# 02.net
KiCad netlist of a schematic drawn in Altium Designer
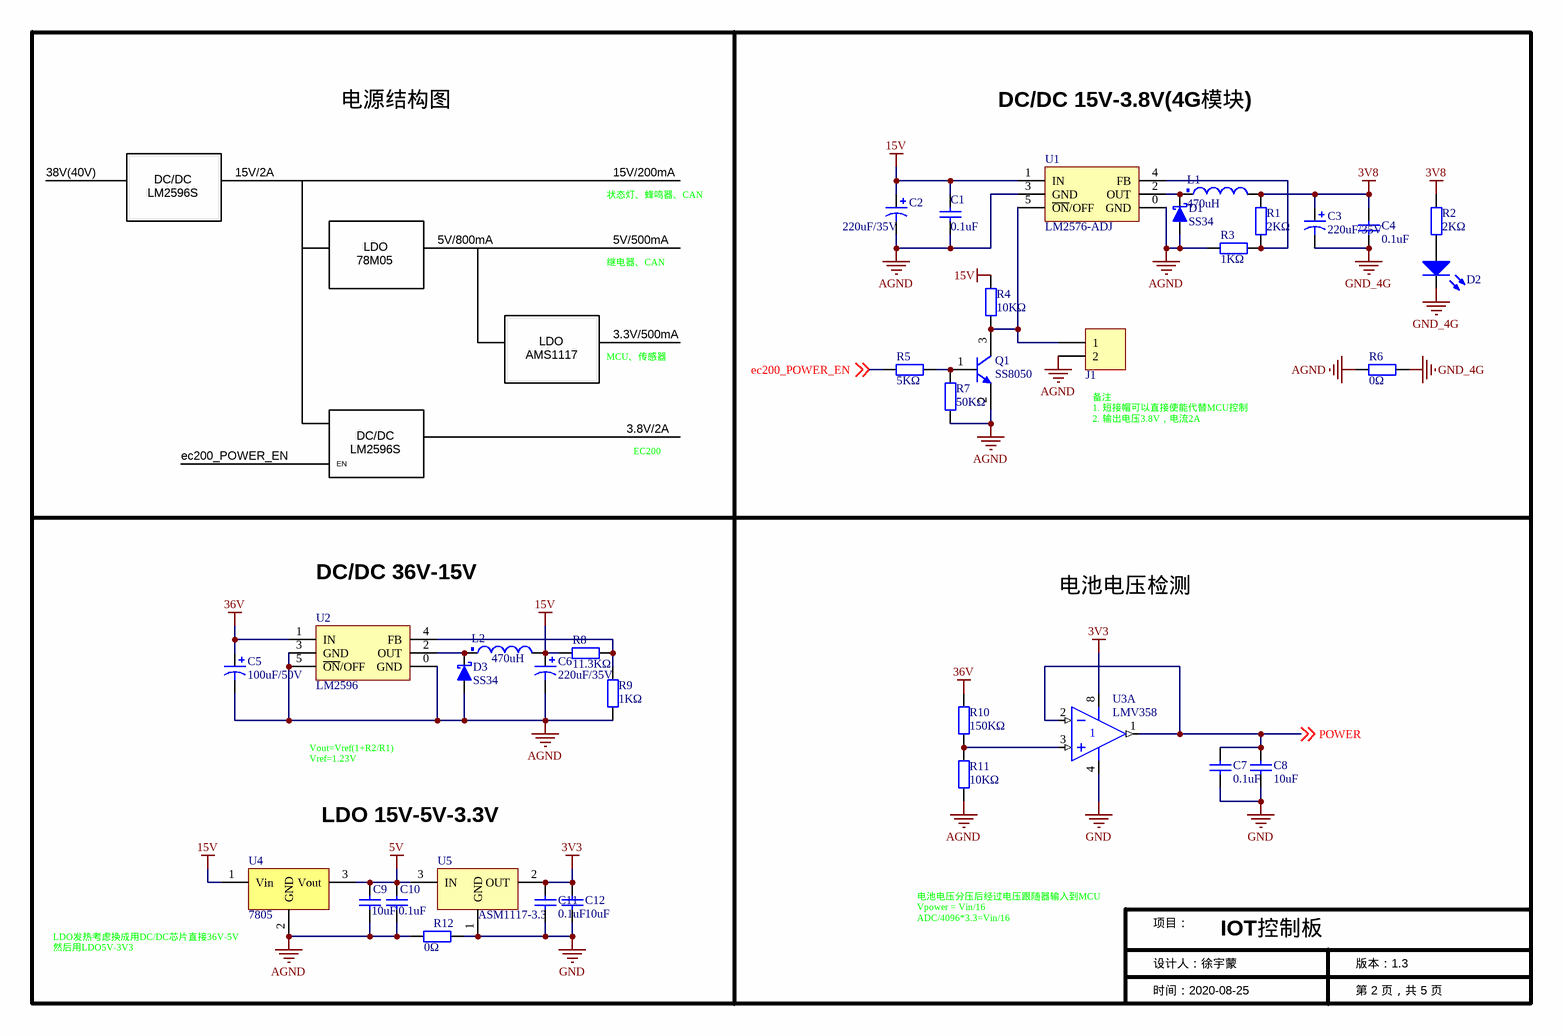
[diagram p0: 02_电源部分.SchDoc]

(export (version "E")
  (design (tool "Eeschema 10.0.6"))
  (components
    (comp (ref "C1")
      (value "0.1uF")
      (footprint "CAP-0603")
      (description "无极性电容")
      (fields (field (name "Comment") "Cap") (field (name "PUBLISHER") "Altium Limited"))
      (libsource (lib "Arrowy_Racing") (part "Cap"))
    )
    (comp (ref "C2")
      (value "220uF/35V")
      (footprint "Cap8x10.5mm")
      (description "贴片电解电容 8*10.5mm")
      (fields (field (name "Comment") "Cap Pol") (field (name "PUBLISHER") "Altium Limited"))
      (libsource (lib "元件库") (part "Cap Pol"))
    )
    (comp (ref "C3")
      (value "220uF/35V")
      (footprint "Cap8x10.5mm")
      (description "贴片电解电容 8*10.5mm")
      (fields (field (name "Comment") "Cap Pol") (field (name "PUBLISHER") "Altium Limited"))
      (libsource (lib "元件库") (part "Cap Pol"))
    )
    (comp (ref "C4")
      (value "0.1uF")
      (footprint "CAP-0603")
      (description "无极性电容")
      (fields (field (name "Comment") "Cap") (field (name "PUBLISHER") "Altium Limited"))
      (libsource (lib "Arrowy_Racing") (part "Cap"))
    )
    (comp (ref "C5")
      (value "100uF/50V")
      (footprint "Cap8x10.5mm")
      (description "贴片电解电容 8*10.5mm")
      (fields (field (name "Comment") "Cap Pol") (field (name "PUBLISHER") "Altium Limited"))
      (libsource (lib "元件库") (part "Cap Pol"))
    )
    (comp (ref "C6")
      (value "220uF/35V")
      (footprint "Cap8x10.5mm")
      (description "贴片电解电容 8*10.5mm")
      (fields (field (name "Comment") "Cap Pol") (field (name "PUBLISHER") "Altium Limited"))
      (libsource (lib "元件库") (part "Cap Pol"))
    )
    (comp (ref "C7")
      (value "0.1uF")
      (footprint "CAP-0603")
      (description "无极性电容")
      (fields (field (name "Comment") "Cap") (field (name "PUBLISHER") "Altium Limited"))
      (libsource (lib "Arrowy_Racing") (part "Cap"))
    )
    (comp (ref "C8")
      (value "10uF")
      (footprint "CAP-0603")
      (description "无极性电容")
      (fields (field (name "Comment") "Cap") (field (name "PUBLISHER") "Altium Limited"))
      (libsource (lib "Arrowy_Racing") (part "Cap"))
    )
    (comp (ref "C9")
      (value "10uF")
      (footprint "CAP-0603")
      (description "无极性电容")
      (fields (field (name "Comment") "Cap") (field (name "PUBLISHER") "Altium Limited"))
      (libsource (lib "Arrowy_Racing") (part "Cap"))
    )
    (comp (ref "C10")
      (value "0.1uF")
      (footprint "CAP-0603")
      (description "无极性电容")
      (fields (field (name "Comment") "Cap") (field (name "PUBLISHER") "Altium Limited"))
      (libsource (lib "Arrowy_Racing") (part "Cap"))
    )
    (comp (ref "C11")
      (value "0.1uF")
      (footprint "CAP-0603")
      (description "无极性电容")
      (fields (field (name "Comment") "Cap") (field (name "PUBLISHER") "Altium Limited"))
      (libsource (lib "Arrowy_Racing") (part "Cap"))
    )
    (comp (ref "C12")
      (value "10uF")
      (footprint "CAP-0603")
      (description "无极性电容")
      (fields (field (name "Comment") "Cap") (field (name "PUBLISHER") "Altium Limited"))
      (libsource (lib "Arrowy_Racing") (part "Cap"))
    )
    (comp (ref "D1")
      (value "SS34")
      (footprint "SMA(DO-214AC)")
      (description "Schottky Diode")
      (fields (field (name "PUBLISHER") "Altium Limited"))
      (libsource (lib "元件库") (part "D Schottky"))
    )
    (comp (ref "D2")
      (value "LED")
      (footprint "LED_0805")
      (description "发光二极管")
      (fields (field (name "PUBLISHER") "Altium Limited"))
      (libsource (lib "Arrowy_Racing") (part "LED"))
    )
    (comp (ref "D3")
      (value "SS34")
      (footprint "SMA(DO-214AC)")
      (description "Schottky Diode")
      (fields (field (name "PUBLISHER") "Altium Limited"))
      (libsource (lib "元件库") (part "D Schottky"))
    )
    (comp (ref "J1")
      (value "Header 2")
      (footprint "Header_2X1_2.54")
      (description "接插件")
      (fields (field (name "PUBLISHER") "Altium Limited"))
      (libsource (lib "Arrowy_Racing") (part "Header 2"))
    )
    (comp (ref "L1")
      (value "470uH")
      (footprint "CD43")
      (description "贴片功率电感")
      (fields (field (name "Comment") "Inductor") (field (name "PUBLISHER") "Altium Limited"))
      (libsource (lib "元件库") (part "Inductor"))
    )
    (comp (ref "L2")
      (value "470uH")
      (footprint "CD43")
      (description "贴片功率电感")
      (fields (field (name "Comment") "Inductor") (field (name "PUBLISHER") "Altium Limited"))
      (libsource (lib "元件库") (part "Inductor"))
    )
    (comp (ref "Q1")
      (value "SS8050")
      (footprint "SOT-23")
      (description "NPN贴片三极管")
      (fields (field (name "PUBLISHER") "Altium Limited"))
      (libsource (lib "Arrowy_Racing") (part "SS8050"))
    )
    (comp (ref "R1")
      (value "2KΩ")
      (footprint "0603")
      (description "贴片电阻")
      (fields (field (name "Comment") "Res") (field (name "PUBLISHER") "Altium Limited"))
      (libsource (lib "") (part "Res_2"))
    )
    (comp (ref "R2")
      (value "2KΩ")
      (footprint "0603")
      (description "贴片电阻")
      (fields (field (name "Comment") "Res") (field (name "PUBLISHER") "Altium Limited"))
      (libsource (lib "Arrowy_Racing") (part "Res"))
    )
    (comp (ref "R3")
      (value "1KΩ")
      (footprint "0603")
      (description "贴片电阻")
      (fields (field (name "Comment") "Res") (field (name "PUBLISHER") "Altium Limited"))
      (libsource (lib "") (part "Res_1"))
    )
    (comp (ref "R4")
      (value "10KΩ")
      (footprint "0603")
      (description "贴片电阻")
      (fields (field (name "Comment") "Res") (field (name "PUBLISHER") "Altium Limited"))
      (libsource (lib "") (part "Res_2"))
    )
    (comp (ref "R5")
      (value "5KΩ")
      (footprint "0603")
      (description "贴片电阻")
      (fields (field (name "Comment") "Res") (field (name "PUBLISHER") "Altium Limited"))
      (libsource (lib "") (part "Res_1"))
    )
    (comp (ref "R6")
      (value "0Ω")
      (footprint "0805")
      (description "贴片电阻")
      (fields (field (name "Comment") "Res") (field (name "PUBLISHER") "Altium Limited"))
      (libsource (lib "") (part "Res_1"))
    )
    (comp (ref "R7")
      (value "50KΩ")
      (footprint "0603")
      (description "贴片电阻")
      (fields (field (name "Comment") "Res") (field (name "PUBLISHER") "Altium Limited"))
      (libsource (lib "") (part "Res_2"))
    )
    (comp (ref "R8")
      (value "11.3KΩ")
      (footprint "0603")
      (description "贴片电阻")
      (fields (field (name "Comment") "Res") (field (name "PUBLISHER") "Altium Limited"))
      (libsource (lib "") (part "Res_1"))
    )
    (comp (ref "R9")
      (value "1KΩ")
      (footprint "0603")
      (description "贴片电阻")
      (fields (field (name "Comment") "Res") (field (name "PUBLISHER") "Altium Limited"))
      (libsource (lib "Arrowy_Racing") (part "Res"))
    )
    (comp (ref "R10")
      (value "150KΩ")
      (footprint "0603")
      (description "贴片电阻")
      (fields (field (name "Comment") "Res") (field (name "PUBLISHER") "Altium Limited"))
      (libsource (lib "Arrowy_Racing") (part "Res"))
    )
    (comp (ref "R11")
      (value "10KΩ")
      (footprint "0603")
      (description "贴片电阻")
      (fields (field (name "Comment") "Res") (field (name "PUBLISHER") "Altium Limited"))
      (libsource (lib "Arrowy_Racing") (part "Res"))
    )
    (comp (ref "R12")
      (value "0Ω")
      (footprint "0805")
      (description "贴片电阻")
      (fields (field (name "Comment") "Res") (field (name "PUBLISHER") "Altium Limited"))
      (libsource (lib "") (part "Res_1"))
    )
    (comp (ref "U1")
      (value "LM2576-ADJ")
      (footprint "TO-263-5 无背面散热")
      (libsource (lib "Arrowy_Racing") (part "LM2576"))
    )
    (comp (ref "U2")
      (value "LM2596")
      (footprint "TO-263-5 无背面散热")
      (description "DC/DC")
      (libsource (lib "Arrowy_Racing") (part "LM2596"))
    )
    (comp (ref "U3")
      (value "LMV358")
      (footprint "OPA2350")
      (fields (field (name "PUBLISHER") "Altium Limited"))
      (libsource (lib "元件库") (part "LMV358"))
    )
    (comp (ref "U4")
      (value "7805")
      (footprint "TO-252")
      (description "三端稳压器7805")
      (libsource (lib "Arrowy_Racing") (part "7805"))
    )
    (comp (ref "U5")
      (value "ASM1117-3.3")
      (footprint "SOT-223")
      (description "3.3V稳压芯片")
      (libsource (lib "Arrowy_Racing") (part "ASM1117"))
    )
  )
  (nets
    (net (code "1") (name "3V3") (class "Default")
      (node (ref "C11") (pin "2") (pinfunction "2_2") (pintype "passive"))
      (node (ref "C12") (pin "2") (pinfunction "2_2") (pintype "passive"))
      (node (ref "U3") (pin "8") (pinfunction "V+_8") (pintype "power_in"))
      (node (ref "U5") (pin "2") (pinfunction "OUT_2") (pintype "passive"))
    )
    (net (code "2") (name "3V8") (class "Default")
      (node (ref "C3") (pin "1") (pinfunction "1_1") (pintype "passive"))
      (node (ref "C4") (pin "2") (pinfunction "2_2") (pintype "passive"))
      (node (ref "L1") (pin "2") (pinfunction "2_2") (pintype "passive"))
      (node (ref "R1") (pin "1") (pinfunction "1_1") (pintype "passive"))
      (node (ref "R2") (pin "2") (pinfunction "2_2") (pintype "passive"))
    )
    (net (code "3") (name "5V") (class "Default")
      (node (ref "C10") (pin "2") (pinfunction "2_2") (pintype "passive"))
      (node (ref "C9") (pin "2") (pinfunction "2_2") (pintype "passive"))
      (node (ref "U4") (pin "3") (pinfunction "Vout_3") (pintype "passive"))
      (node (ref "U5") (pin "3") (pinfunction "IN_3") (pintype "passive"))
    )
    (net (code "4") (name "15V") (class "Default")
      (node (ref "C1") (pin "2") (pinfunction "2_2") (pintype "passive"))
      (node (ref "C2") (pin "1") (pinfunction "1_1") (pintype "passive"))
      (node (ref "C6") (pin "1") (pinfunction "1_1") (pintype "passive"))
      (node (ref "L2") (pin "2") (pinfunction "2_2") (pintype "passive"))
      (node (ref "R4") (pin "1") (pinfunction "1_1") (pintype "passive"))
      (node (ref "R8") (pin "1") (pinfunction "1_1") (pintype "passive"))
      (node (ref "U1") (pin "1") (pinfunction "IN_1") (pintype "passive"))
      (node (ref "U4") (pin "1") (pinfunction "Vin_1") (pintype "passive"))
    )
    (net (code "5") (name "36V") (class "Default")
      (node (ref "C5") (pin "1") (pinfunction "1_1") (pintype "passive"))
      (node (ref "R10") (pin "2") (pinfunction "2_2") (pintype "passive"))
      (node (ref "U2") (pin "1") (pinfunction "IN_1") (pintype "passive"))
    )
    (net (code "6") (name "AGND") (class "Default")
      (node (ref "C1") (pin "1") (pinfunction "1_1") (pintype "passive"))
      (node (ref "C10") (pin "1") (pinfunction "1_1") (pintype "passive"))
      (node (ref "C2") (pin "2") (pinfunction "2_2") (pintype "passive"))
      (node (ref "C5") (pin "2") (pinfunction "2_2") (pintype "passive"))
      (node (ref "C6") (pin "2") (pinfunction "2_2") (pintype "passive"))
      (node (ref "C9") (pin "1") (pinfunction "1_1") (pintype "passive"))
      (node (ref "D1") (pin "1") (pinfunction "A_1") (pintype "passive"))
      (node (ref "D3") (pin "1") (pinfunction "A_1") (pintype "passive"))
      (node (ref "J1") (pin "2") (pinfunction "2_2") (pintype "passive"))
      (node (ref "Q1") (pin "2") (pinfunction "E_2") (pintype "passive"))
      (node (ref "R11") (pin "1") (pinfunction "1_1") (pintype "passive"))
      (node (ref "R12") (pin "1") (pinfunction "1_1") (pintype "passive"))
      (node (ref "R3") (pin "1") (pinfunction "1_1") (pintype "passive"))
      (node (ref "R6") (pin "1") (pinfunction "1_1") (pintype "passive"))
      (node (ref "R7") (pin "2") (pinfunction "2_2") (pintype "passive"))
      (node (ref "R9") (pin "1") (pinfunction "1_1") (pintype "passive"))
      (node (ref "U1") (pin "0") (pinfunction "GND_0") (pintype "passive"))
      (node (ref "U1") (pin "3") (pinfunction "GND_3") (pintype "passive"))
      (node (ref "U2") (pin "0") (pinfunction "GND_0") (pintype "passive"))
      (node (ref "U2") (pin "3") (pinfunction "GND_3") (pintype "passive"))
      (node (ref "U2") (pin "5") (pinfunction "~{ON}/OFF_5") (pintype "passive"))
      (node (ref "U4") (pin "2") (pinfunction "GND_2") (pintype "passive"))
    )
    (net (code "7") (name "GND") (class "Default")
      (node (ref "C11") (pin "1") (pinfunction "1_1") (pintype "passive"))
      (node (ref "C12") (pin "1") (pinfunction "1_1") (pintype "passive"))
      (node (ref "C7") (pin "1") (pinfunction "1_1") (pintype "passive"))
      (node (ref "C8") (pin "1") (pinfunction "1_1") (pintype "passive"))
      (node (ref "R12") (pin "2") (pinfunction "2_2") (pintype "passive"))
      (node (ref "U3") (pin "4") (pinfunction "V-_4") (pintype "power_in"))
      (node (ref "U5") (pin "1") (pinfunction "GND_1") (pintype "passive"))
    )
    (net (code "8") (name "GND_4G") (class "Default")
      (node (ref "C3") (pin "2") (pinfunction "2_2") (pintype "passive"))
      (node (ref "C4") (pin "1") (pinfunction "1_1") (pintype "passive"))
      (node (ref "D2") (pin "2") (pinfunction "K_2") (pintype "passive"))
      (node (ref "R6") (pin "2") (pinfunction "2_2") (pintype "passive"))
    )
    (net (code "9") (name "Net-(D1-K)") (class "Default")
      (node (ref "D1") (pin "2") (pinfunction "K_2") (pintype "passive"))
      (node (ref "L1") (pin "1") (pinfunction "1_1") (pintype "passive"))
      (node (ref "U1") (pin "2") (pinfunction "OUT_2") (pintype "passive"))
    )
    (net (code "10") (name "Net-(D2-A)") (class "Default")
      (node (ref "D2") (pin "1") (pinfunction "A_1") (pintype "passive"))
      (node (ref "R2") (pin "1") (pinfunction "1_1") (pintype "passive"))
    )
    (net (code "11") (name "Net-(D3-K)") (class "Default")
      (node (ref "D3") (pin "2") (pinfunction "K_2") (pintype "passive"))
      (node (ref "L2") (pin "1") (pinfunction "1_1") (pintype "passive"))
      (node (ref "U2") (pin "2") (pinfunction "OUT_2") (pintype "passive"))
    )
    (net (code "12") (name "Net-(Q1-B)") (class "Default")
      (node (ref "Q1") (pin "1") (pinfunction "B_1") (pintype "passive"))
      (node (ref "R5") (pin "2") (pinfunction "2_2") (pintype "passive"))
      (node (ref "R7") (pin "1") (pinfunction "1_1") (pintype "passive"))
    )
    (net (code "13") (name "Net-(Q1-C)") (class "Default")
      (node (ref "J1") (pin "1") (pinfunction "1_1") (pintype "passive"))
      (node (ref "Q1") (pin "3") (pinfunction "C_3") (pintype "passive"))
      (node (ref "R4") (pin "2") (pinfunction "2_2") (pintype "passive"))
      (node (ref "U1") (pin "5") (pinfunction "~{ON}/OFF_5") (pintype "passive"))
    )
    (net (code "14") (name "Net-(U1-FB)") (class "Default")
      (node (ref "R1") (pin "2") (pinfunction "2_2") (pintype "passive"))
      (node (ref "R3") (pin "2") (pinfunction "2_2") (pintype "passive"))
      (node (ref "U1") (pin "4") (pinfunction "FB_4") (pintype "passive"))
    )
    (net (code "15") (name "Net-(U2-FB)") (class "Default")
      (node (ref "R8") (pin "2") (pinfunction "2_2") (pintype "passive"))
      (node (ref "R9") (pin "2") (pinfunction "2_2") (pintype "passive"))
      (node (ref "U2") (pin "4") (pinfunction "FB_4") (pintype "passive"))
    )
    (net (code "16") (name "Net-(U3A-IN+)") (class "Default")
      (node (ref "R10") (pin "1") (pinfunction "1_1") (pintype "passive"))
      (node (ref "R11") (pin "2") (pinfunction "2_2") (pintype "passive"))
      (node (ref "U3") (pin "3") (pinfunction "IN+_3") (pintype "input"))
    )
    (net (code "17") (name "POWER") (class "Default")
      (node (ref "C7") (pin "2") (pinfunction "2_2") (pintype "passive"))
      (node (ref "C8") (pin "2") (pinfunction "2_2") (pintype "passive"))
      (node (ref "U3") (pin "1") (pinfunction "OUT_1") (pintype "output"))
      (node (ref "U3") (pin "2") (pinfunction "IN-_2") (pintype "input"))
    )
    (net (code "18") (name "ec200_POWER_EN") (class "Default")
      (node (ref "R5") (pin "1") (pinfunction "1_1") (pintype "passive"))
    )
  )
)
